# USB_OTG.net
KiCad netlist of a schematic drawn in Altium Designer
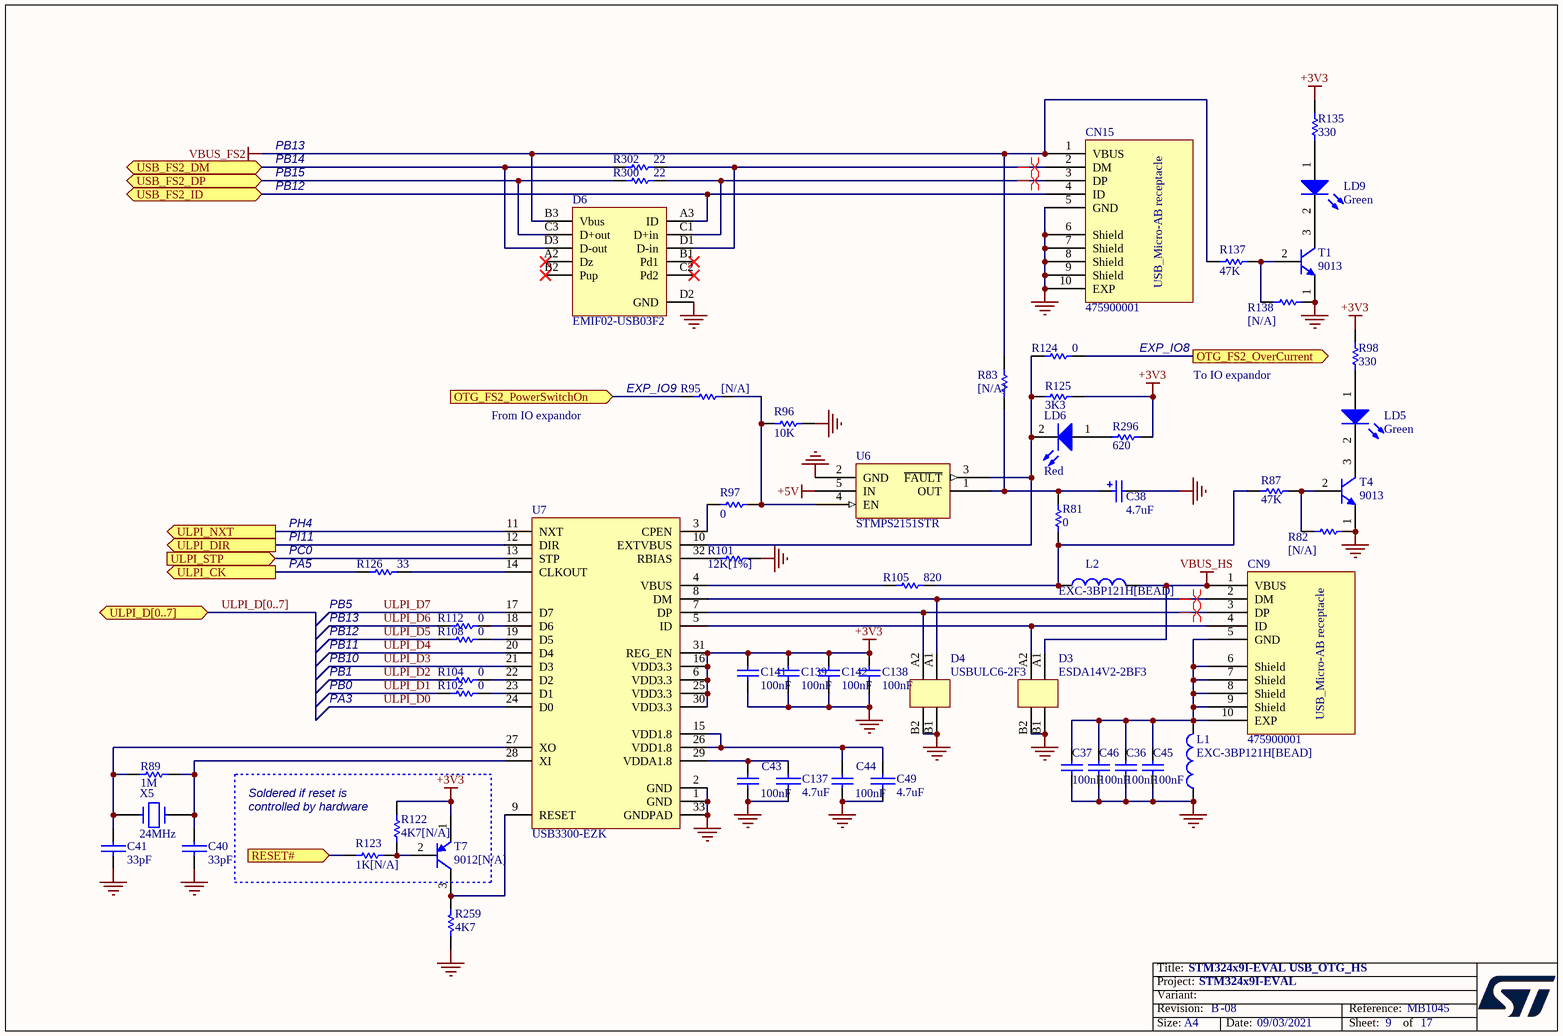
[diagram p0: USB_OTG.SchDoc]

(export (version "E")
  (design (tool "Eeschema 10.0.6"))
  (components
    (comp (ref "C36")
      (value "100nF")
      (footprint "0603C")
      (description "Capacitor")
      (fields (field (name "PUBLISHER") "Altium Limited"))
      (libsource (lib "Miscellaneous Devices") (part "Cap"))
    )
    (comp (ref "C37")
      (value "100nF")
      (footprint "0603C")
      (description "Capacitor")
      (fields (field (name "PUBLISHER") "Altium Limited"))
      (libsource (lib "Miscellaneous Devices") (part "Cap"))
    )
    (comp (ref "C38")
      (value "4.7uF")
      (footprint "TAN-A")
      (description "Polarized Capacitor (Radial)")
      (fields (field (name "PUBLISHER") "Altium Limited"))
      (libsource (lib "Miscellaneous Devices") (part "Cap Pol1"))
    )
    (comp (ref "C40")
      (value "33pF")
      (footprint "0603C")
      (description "Capacitor")
      (libsource (lib "*") (part "CAP"))
    )
    (comp (ref "C41")
      (value "33pF")
      (footprint "0603C")
      (description "Capacitor")
      (libsource (lib "*") (part "CAP"))
    )
    (comp (ref "C43")
      (value "100nF")
      (footprint "0603C")
      (description "Capacitor")
      (fields (field (name "PUBLISHER") "Altium Limited"))
      (libsource (lib "Miscellaneous Devices") (part "Cap"))
    )
    (comp (ref "C44")
      (value "100nF")
      (footprint "0603C")
      (description "Capacitor")
      (fields (field (name "PUBLISHER") "Altium Limited"))
      (libsource (lib "Miscellaneous Devices") (part "Cap"))
    )
    (comp (ref "C45")
      (value "100nF")
      (footprint "0603C")
      (description "Capacitor")
      (fields (field (name "PUBLISHER") "Altium Limited"))
      (libsource (lib "Miscellaneous Devices") (part "Cap"))
    )
    (comp (ref "C46")
      (value "100nF")
      (footprint "0603C")
      (description "Capacitor")
      (fields (field (name "PUBLISHER") "Altium Limited"))
      (libsource (lib "Miscellaneous Devices") (part "Cap"))
    )
    (comp (ref "C49")
      (value "4.7uF")
      (footprint "TAN-A")
      (description "Capacitor")
      (libsource (lib "") (part "CAP_1"))
    )
    (comp (ref "C137")
      (value "4.7uF")
      (footprint "TAN-A")
      (description "Capacitor")
      (libsource (lib "") (part "CAP_1"))
    )
    (comp (ref "C138")
      (value "100nF")
      (footprint "0603C")
      (description "Capacitor")
      (fields (field (name "PUBLISHER") "Altium Limited"))
      (libsource (lib "Miscellaneous Devices") (part "Cap"))
    )
    (comp (ref "C139")
      (value "100nF")
      (footprint "0603C")
      (description "Capacitor")
      (fields (field (name "PUBLISHER") "Altium Limited"))
      (libsource (lib "Miscellaneous Devices") (part "Cap"))
    )
    (comp (ref "C141")
      (value "100nF")
      (footprint "0603C")
      (description "Capacitor")
      (fields (field (name "PUBLISHER") "Altium Limited"))
      (libsource (lib "Miscellaneous Devices") (part "Cap"))
    )
    (comp (ref "C142")
      (value "100nF")
      (footprint "0603C")
      (description "Capacitor")
      (fields (field (name "PUBLISHER") "Altium Limited"))
      (libsource (lib "Miscellaneous Devices") (part "Cap"))
    )
    (comp (ref "CN9")
      (value "475900001")
      (footprint "MOLEX_47590001")
      (libsource (lib "mb1045") (part "475900001"))
    )
    (comp (ref "CN15")
      (value "475900001")
      (footprint "MOLEX_47590001")
      (libsource (lib "mb1045") (part "475900001"))
    )
    (comp (ref "D3")
      (value "ESDA14V2-2BF3")
      (footprint "BGA4_0R4_0R8X0R8")
      (libsource (lib "MB786") (part "ESDA14V2-2BF3"))
    )
    (comp (ref "D4")
      (value "USBULC6-2F3")
      (footprint "BGA4_0R4_1X1")
      (libsource (lib "MB786") (part "USBULC6-2F3"))
    )
    (comp (ref "D6")
      (value "EMIF02-USB03F2")
      (footprint "BGA11_0R5_1R57X2R07")
      (libsource (lib "mb1045") (part "EMIF02-USB03F2"))
    )
    (comp (ref "L1")
      (value "EXC-3BP121H[BEAD]")
      (footprint "0603L")
      (description "Inductor")
      (fields (field (name "PUBLISHER") "Altium Limited"))
      (libsource (lib "Miscellaneous Devices") (part "Inductor"))
    )
    (comp (ref "L2")
      (value "EXC-3BP121H[BEAD]")
      (footprint "0603L")
      (description "Inductor")
      (fields (field (name "PUBLISHER") "Altium Limited"))
      (libsource (lib "Miscellaneous Devices") (part "Inductor"))
    )
    (comp (ref "LD5")
      (value "Green")
      (footprint "0603D")
      (description "Typical RED, GREEN, YELLOW, AMBER GaAs LED")
      (fields (field (name "PUBLISHER") "Altium Limited"))
      (libsource (lib "Miscellaneous Devices") (part "LED2"))
    )
    (comp (ref "LD6")
      (value "Red")
      (footprint "0603D")
      (description "Typical RED, GREEN, YELLOW, AMBER GaAs LED")
      (fields (field (name "PUBLISHER") "Altium Limited"))
      (libsource (lib "Miscellaneous Devices") (part "LED2"))
    )
    (comp (ref "LD9")
      (value "Green")
      (footprint "0603D")
      (description "Typical RED, GREEN, YELLOW, AMBER GaAs LED")
      (fields (field (name "PUBLISHER") "Altium Limited"))
      (libsource (lib "Miscellaneous Devices") (part "LED2"))
    )
    (comp (ref "R81")
      (value "0")
      (footprint "0603R")
      (description "Resistor")
      (fields (field (name "PUBLISHER") "Altium Limited"))
      (libsource (lib "Miscellaneous Devices") (part "Res1"))
    )
    (comp (ref "R82")
      (value "[N/A]")
      (footprint "0603R")
      (description "Resistor")
      (fields (field (name "PUBLISHER") "Altium Limited"))
      (libsource (lib "Miscellaneous Devices") (part "res1"))
    )
    (comp (ref "R83")
      (value "[N/A]")
      (footprint "0603R")
      (description "Resistor")
      (fields (field (name "PUBLISHER") "Altium Limited"))
      (libsource (lib "Miscellaneous Devices") (part "Res1"))
    )
    (comp (ref "R87")
      (value "47K")
      (footprint "0603R")
      (description "Resistor")
      (fields (field (name "PUBLISHER") "Altium Limited"))
      (libsource (lib "Miscellaneous Devices") (part "res1"))
    )
    (comp (ref "R89")
      (value "1M")
      (footprint "0603R")
      (description "Resistor")
      (fields (field (name "PUBLISHER") "Altium Limited"))
      (libsource (lib "Miscellaneous Devices") (part "Res1"))
    )
    (comp (ref "R95")
      (value "[N/A]")
      (footprint "0603R")
      (description "Resistor")
      (fields (field (name "PUBLISHER") "Altium Limited"))
      (libsource (lib "Miscellaneous Devices") (part "Res1"))
    )
    (comp (ref "R96")
      (value "10K")
      (footprint "0603R")
      (description "Resistor")
      (fields (field (name "PUBLISHER") "Altium Limited"))
      (libsource (lib "Miscellaneous Devices") (part "res1"))
    )
    (comp (ref "R97")
      (value "0")
      (footprint "0603R")
      (description "Resistor")
      (fields (field (name "PUBLISHER") "Altium Limited"))
      (libsource (lib "Miscellaneous Devices") (part "Res1"))
    )
    (comp (ref "R98")
      (value "330")
      (footprint "0603R")
      (description "Resistor")
      (fields (field (name "PUBLISHER") "Altium Limited"))
      (libsource (lib "Miscellaneous Devices") (part "res1"))
    )
    (comp (ref "R101")
      (value "12K[1%]")
      (footprint "0603R")
      (description "Resistor")
      (fields (field (name "PUBLISHER") "Altium Limited"))
      (libsource (lib "Miscellaneous Devices") (part "Res1"))
    )
    (comp (ref "R102")
      (value "0")
      (footprint "0603R")
      (description "Resistor")
      (fields (field (name "PUBLISHER") "Altium Limited"))
      (libsource (lib "Miscellaneous Devices") (part "Res1"))
    )
    (comp (ref "R104")
      (value "0")
      (footprint "0603R")
      (description "Resistor")
      (fields (field (name "PUBLISHER") "Altium Limited"))
      (libsource (lib "Miscellaneous Devices") (part "Res1"))
    )
    (comp (ref "R105")
      (value "820")
      (footprint "0603R")
      (description "Resistor")
      (fields (field (name "PUBLISHER") "Altium Limited"))
      (libsource (lib "Miscellaneous Devices") (part "res1"))
    )
    (comp (ref "R108")
      (value "0")
      (footprint "0603R")
      (description "Resistor")
      (fields (field (name "PUBLISHER") "Altium Limited"))
      (libsource (lib "Miscellaneous Devices") (part "Res1"))
    )
    (comp (ref "R112")
      (value "0")
      (footprint "0603R")
      (description "Resistor")
      (fields (field (name "PUBLISHER") "Altium Limited"))
      (libsource (lib "Miscellaneous Devices") (part "Res1"))
    )
    (comp (ref "R122")
      (value "4K7[N/A]")
      (footprint "0603R")
      (description "Resistor")
      (fields (field (name "PUBLISHER") "Altium Limited"))
      (libsource (lib "*") (part "Res1"))
    )
    (comp (ref "R123")
      (value "1K[N/A]")
      (footprint "0603R")
      (description "Resistor")
      (fields (field (name "PUBLISHER") "Altium Limited"))
      (libsource (lib "Miscellaneous Devices") (part "Res1"))
    )
    (comp (ref "R124")
      (value "0")
      (footprint "0603R")
      (description "Resistor")
      (fields (field (name "PUBLISHER") "Altium Limited"))
      (libsource (lib "Miscellaneous Devices") (part "Res1"))
    )
    (comp (ref "R125")
      (value "3K3")
      (footprint "0603R")
      (description "Resistor")
      (fields (field (name "PUBLISHER") "Altium Limited"))
      (libsource (lib "Miscellaneous Devices") (part "res1"))
    )
    (comp (ref "R126")
      (value "33")
      (footprint "0603R")
      (description "Resistor")
      (fields (field (name "PUBLISHER") "Altium Limited"))
      (libsource (lib "Miscellaneous Devices") (part "Res1"))
    )
    (comp (ref "R135")
      (value "330")
      (footprint "0603R")
      (description "Resistor")
      (fields (field (name "PUBLISHER") "Altium Limited"))
      (libsource (lib "Miscellaneous Devices") (part "res1"))
    )
    (comp (ref "R137")
      (value "47K")
      (footprint "0603R")
      (description "Resistor")
      (fields (field (name "PUBLISHER") "Altium Limited"))
      (libsource (lib "Miscellaneous Devices") (part "res1"))
    )
    (comp (ref "R138")
      (value "[N/A]")
      (footprint "0603R")
      (description "Resistor")
      (fields (field (name "PUBLISHER") "Altium Limited"))
      (libsource (lib "Miscellaneous Devices") (part "res1"))
    )
    (comp (ref "R259")
      (value "4K7")
      (footprint "0603R")
      (description "Resistor")
      (fields (field (name "PUBLISHER") "Altium Limited"))
      (libsource (lib "*") (part "Res1"))
    )
    (comp (ref "R296")
      (value "620")
      (footprint "0603R")
      (description "Resistor")
      (fields (field (name "PUBLISHER") "Altium Limited"))
      (libsource (lib "Miscellaneous Devices") (part "Res1"))
    )
    (comp (ref "R300")
      (value "22")
      (footprint "0603R")
      (description "Resistor")
      (fields (field (name "PUBLISHER") "Altium Limited"))
      (libsource (lib "Miscellaneous Devices") (part "Res1"))
    )
    (comp (ref "R302")
      (value "22")
      (footprint "0603R")
      (description "Resistor")
      (fields (field (name "PUBLISHER") "Altium Limited"))
      (libsource (lib "Miscellaneous Devices") (part "Res1"))
    )
    (comp (ref "T1")
      (value "9013")
      (footprint "SOT23-213")
      (description "NPN Bipolar Transistor")
      (fields (field (name "PUBLISHER") "Altium Limited"))
      (libsource (lib "mb1045") (part "NPN"))
    )
    (comp (ref "T4")
      (value "9013")
      (footprint "SOT23-213")
      (description "NPN Bipolar Transistor")
      (fields (field (name "PUBLISHER") "Altium Limited"))
      (libsource (lib "mb1045") (part "NPN"))
    )
    (comp (ref "T7")
      (value "9012[N/A]")
      (footprint "SOT23-213")
      (description "PNP Bipolar Transistor")
      (fields (field (name "PUBLISHER") "Altium Limited"))
      (libsource (lib "Miscellaneous Devices") (part "PNP"))
    )
    (comp (ref "U6")
      (value "STMPS2151STR")
      (footprint "SOT23-5")
      (libsource (lib "mb1045") (part "STMPS2141STR"))
    )
    (comp (ref "U7")
      (value "USB3300-EZK")
      (footprint "QFN32_0R5_5X5")
      (libsource (lib "MB1000_1") (part "USB3300-EZK"))
    )
    (comp (ref "X5")
      (value "24MHz")
      (footprint "XTAL1")
      (description "Crystal")
      (libsource (lib "*") (part "CRYSTAL"))
    )
  )
  (nets
    (net (code "1") (name "+3V3") (class "Default")
      (node (ref "C138") (pin "1") (pinfunction "1_1") (pintype "passive"))
      (node (ref "C139") (pin "1") (pinfunction "1_1") (pintype "passive"))
      (node (ref "C141") (pin "1") (pinfunction "1_1") (pintype "passive"))
      (node (ref "C142") (pin "1") (pinfunction "1_1") (pintype "passive"))
      (node (ref "R122") (pin "1") (pinfunction "1_1") (pintype "passive"))
      (node (ref "R125") (pin "1") (pinfunction "1_1") (pintype "passive"))
      (node (ref "R135") (pin "2") (pinfunction "2_2") (pintype "passive"))
      (node (ref "R296") (pin "2") (pinfunction "2_2") (pintype "passive"))
      (node (ref "R98") (pin "2") (pinfunction "2_2") (pintype "passive"))
      (node (ref "T7") (pin "1") (pinfunction "E_1") (pintype "passive"))
      (node (ref "U7") (pin "16") (pinfunction "VDD3.3_16") (pintype "passive"))
      (node (ref "U7") (pin "25") (pinfunction "VDD3.3_25") (pintype "passive"))
      (node (ref "U7") (pin "30") (pinfunction "VDD3.3_30") (pintype "passive"))
      (node (ref "U7") (pin "31") (pinfunction "REG_EN_31") (pintype "passive"))
      (node (ref "U7") (pin "6") (pinfunction "VDD3.3_6") (pintype "passive"))
    )
    (net (code "2") (name "+5V") (class "Default")
      (node (ref "U6") (pin "5") (pinfunction "IN_5") (pintype "passive"))
    )
    (net (code "3") (name "/OTG_FS2_OverCurrent") (class "Default")
      (node (ref "R124") (pin "1") (pinfunction "1_1") (pintype "passive"))
    )
    (net (code "4") (name "/OTG_FS2_PowerSwitchOn") (class "Default")
      (node (ref "R95") (pin "2") (pinfunction "2_2") (pintype "passive"))
    )
    (net (code "5") (name "/RESET#") (class "Default")
      (node (ref "R123") (pin "2") (pinfunction "2_2") (pintype "passive"))
    )
    (net (code "6") (name "/ULPI_CK") (class "Default")
      (node (ref "R126") (pin "2") (pinfunction "2_2") (pintype "passive"))
    )
    (net (code "7") (name "/ULPI_D0") (class "Default")
      (node (ref "U7") (pin "24") (pinfunction "D0_24") (pintype "passive"))
    )
    (net (code "8") (name "/ULPI_D1") (class "Default")
      (node (ref "R102") (pin "2") (pinfunction "2_2") (pintype "passive"))
    )
    (net (code "9") (name "/ULPI_D2") (class "Default")
      (node (ref "R104") (pin "2") (pinfunction "2_2") (pintype "passive"))
    )
    (net (code "10") (name "/ULPI_D3") (class "Default")
      (node (ref "U7") (pin "21") (pinfunction "D3_21") (pintype "passive"))
    )
    (net (code "11") (name "/ULPI_D4") (class "Default")
      (node (ref "U7") (pin "20") (pinfunction "D4_20") (pintype "passive"))
    )
    (net (code "12") (name "/ULPI_D5") (class "Default")
      (node (ref "R108") (pin "2") (pinfunction "2_2") (pintype "passive"))
    )
    (net (code "13") (name "/ULPI_D6") (class "Default")
      (node (ref "R112") (pin "2") (pinfunction "2_2") (pintype "passive"))
    )
    (net (code "14") (name "/ULPI_D7") (class "Default")
      (node (ref "U7") (pin "17") (pinfunction "D7_17") (pintype "passive"))
    )
    (net (code "15") (name "/ULPI_DIR") (class "Default")
      (node (ref "U7") (pin "12") (pinfunction "DIR_12") (pintype "passive"))
    )
    (net (code "17") (name "/ULPI_NXT") (class "Default")
      (node (ref "U7") (pin "11") (pinfunction "NXT_11") (pintype "passive"))
    )
    (net (code "18") (name "/ULPI_STP") (class "Default")
      (node (ref "U7") (pin "13") (pinfunction "STP_13") (pintype "passive"))
    )
    (net (code "19") (name "/USB_FS2_DM") (class "Default")
      (node (ref "D6") (pin "D3") (pinfunction "D-out_D3") (pintype "passive"))
      (node (ref "R302") (pin "2") (pinfunction "2_2") (pintype "passive"))
    )
    (net (code "20") (name "/USB_FS2_DP") (class "Default")
      (node (ref "D6") (pin "C3") (pinfunction "D+out_C3") (pintype "passive"))
      (node (ref "R300") (pin "2") (pinfunction "2_2") (pintype "passive"))
    )
    (net (code "21") (name "/USB_FS2_ID") (class "Default")
      (node (ref "CN15") (pin "4") (pinfunction "ID_4") (pintype "passive"))
      (node (ref "D6") (pin "A3") (pinfunction "ID_A3") (pintype "passive"))
    )
    (net (code "22") (name "GND") (class "Default")
      (node (ref "C137") (pin "2") (pinfunction "2_2") (pintype "passive"))
      (node (ref "C138") (pin "2") (pinfunction "2_2") (pintype "passive"))
      (node (ref "C139") (pin "2") (pinfunction "2_2") (pintype "passive"))
      (node (ref "C141") (pin "2") (pinfunction "2_2") (pintype "passive"))
      (node (ref "C142") (pin "2") (pinfunction "2_2") (pintype "passive"))
      (node (ref "C36") (pin "2") (pinfunction "2_2") (pintype "passive"))
      (node (ref "C37") (pin "2") (pinfunction "2_2") (pintype "passive"))
      (node (ref "C38") (pin "2") (pinfunction "2_2") (pintype "passive"))
      (node (ref "C40") (pin "2") (pinfunction "2_2") (pintype "passive"))
      (node (ref "C41") (pin "2") (pinfunction "2_2") (pintype "passive"))
      (node (ref "C43") (pin "2") (pinfunction "2_2") (pintype "passive"))
      (node (ref "C44") (pin "2") (pinfunction "2_2") (pintype "passive"))
      (node (ref "C45") (pin "2") (pinfunction "2_2") (pintype "passive"))
      (node (ref "C46") (pin "2") (pinfunction "2_2") (pintype "passive"))
      (node (ref "C49") (pin "2") (pinfunction "2_2") (pintype "passive"))
      (node (ref "CN15") (pin "10") (pinfunction "EXP_10") (pintype "passive"))
      (node (ref "CN15") (pin "5") (pinfunction "GND_5") (pintype "passive"))
      (node (ref "CN15") (pin "6") (pinfunction "Shield_6") (pintype "passive"))
      (node (ref "CN15") (pin "7") (pinfunction "Shield_7") (pintype "passive"))
      (node (ref "CN15") (pin "8") (pinfunction "Shield_8") (pintype "passive"))
      (node (ref "CN15") (pin "9") (pinfunction "Shield_9") (pintype "passive"))
      (node (ref "D3") (pin "B1") (pintype "passive"))
      (node (ref "D3") (pin "B2") (pintype "passive"))
      (node (ref "D4") (pin "B1") (pintype "passive"))
      (node (ref "D4") (pin "B2") (pintype "passive"))
      (node (ref "D6") (pin "D2") (pinfunction "GND_D2") (pintype "passive"))
      (node (ref "L1") (pin "1") (pinfunction "1_1") (pintype "passive"))
      (node (ref "R101") (pin "1") (pinfunction "1_1") (pintype "passive"))
      (node (ref "R138") (pin "1") (pinfunction "1_1") (pintype "passive"))
      (node (ref "R259") (pin "1") (pinfunction "1_1") (pintype "passive"))
      (node (ref "R82") (pin "1") (pinfunction "1_1") (pintype "passive"))
      (node (ref "R96") (pin "1") (pinfunction "1_1") (pintype "passive"))
      (node (ref "T1") (pin "1") (pinfunction "E_1") (pintype "passive"))
      (node (ref "T4") (pin "1") (pinfunction "E_1") (pintype "passive"))
      (node (ref "U6") (pin "2") (pinfunction "GND_2") (pintype "passive"))
      (node (ref "U7") (pin "1") (pinfunction "GND_1") (pintype "passive"))
      (node (ref "U7") (pin "2") (pinfunction "GND_2") (pintype "passive"))
      (node (ref "U7") (pin "33") (pinfunction "GNDPAD_33") (pintype "passive"))
    )
    (net (code "23") (name "Net-(C44-Pad1)") (class "Default")
      (node (ref "C44") (pin "1") (pinfunction "1_1") (pintype "passive"))
      (node (ref "C49") (pin "1") (pinfunction "1_1") (pintype "passive"))
      (node (ref "U7") (pin "15") (pinfunction "VDD1.8_15") (pintype "passive"))
      (node (ref "U7") (pin "26") (pinfunction "VDD1.8_26") (pintype "passive"))
    )
    (net (code "24") (name "Net-(CN9-DM)") (class "Default")
      (node (ref "CN9") (pin "2") (pinfunction "DM_2") (pintype "passive"))
      (node (ref "D4") (pin "A1") (pintype "passive"))
      (node (ref "U7") (pin "8") (pinfunction "DM_8") (pintype "passive"))
    )
    (net (code "25") (name "Net-(CN9-DP)") (class "Default")
      (node (ref "CN9") (pin "3") (pinfunction "DP_3") (pintype "passive"))
      (node (ref "D4") (pin "A2") (pintype "passive"))
      (node (ref "U7") (pin "7") (pinfunction "DP_7") (pintype "passive"))
    )
    (net (code "26") (name "Net-(CN9-EXP)") (class "Default")
      (node (ref "C36") (pin "1") (pinfunction "1_1") (pintype "passive"))
      (node (ref "C37") (pin "1") (pinfunction "1_1") (pintype "passive"))
      (node (ref "C45") (pin "1") (pinfunction "1_1") (pintype "passive"))
      (node (ref "C46") (pin "1") (pinfunction "1_1") (pintype "passive"))
      (node (ref "CN9") (pin "10") (pinfunction "EXP_10") (pintype "passive"))
      (node (ref "CN9") (pin "5") (pinfunction "GND_5") (pintype "passive"))
      (node (ref "CN9") (pin "6") (pinfunction "Shield_6") (pintype "passive"))
      (node (ref "CN9") (pin "7") (pinfunction "Shield_7") (pintype "passive"))
      (node (ref "CN9") (pin "8") (pinfunction "Shield_8") (pintype "passive"))
      (node (ref "CN9") (pin "9") (pinfunction "Shield_9") (pintype "passive"))
      (node (ref "L1") (pin "2") (pinfunction "2_2") (pintype "passive"))
    )
    (net (code "27") (name "Net-(CN9-ID)") (class "Default")
      (node (ref "CN9") (pin "4") (pinfunction "ID_4") (pintype "passive"))
      (node (ref "D3") (pin "A2") (pintype "passive"))
      (node (ref "U7") (pin "5") (pinfunction "ID_5") (pintype "passive"))
    )
    (net (code "28") (name "Net-(CN15-DM)") (class "Default")
      (node (ref "CN15") (pin "2") (pinfunction "DM_2") (pintype "passive"))
      (node (ref "D6") (pin "D1") (pinfunction "D-in_D1") (pintype "passive"))
      (node (ref "R302") (pin "1") (pinfunction "1_1") (pintype "passive"))
    )
    (net (code "29") (name "Net-(CN15-DP)") (class "Default")
      (node (ref "CN15") (pin "3") (pinfunction "DP_3") (pintype "passive"))
      (node (ref "D6") (pin "C1") (pinfunction "D+in_C1") (pintype "passive"))
      (node (ref "R300") (pin "1") (pinfunction "1_1") (pintype "passive"))
    )
    (net (code "30") (name "Net-(L2-Pad1)") (class "Default")
      (node (ref "L2") (pin "1") (pinfunction "1_1") (pintype "passive"))
      (node (ref "R105") (pin "2") (pinfunction "2_2") (pintype "passive"))
      (node (ref "R81") (pin "2") (pinfunction "2_2") (pintype "passive"))
      (node (ref "R87") (pin "2") (pinfunction "2_2") (pintype "passive"))
    )
    (net (code "31") (name "Net-(LD5-A)") (class "Default")
      (node (ref "LD5") (pin "1") (pinfunction "A_1") (pintype "passive"))
      (node (ref "R98") (pin "1") (pinfunction "1_1") (pintype "passive"))
    )
    (net (code "32") (name "Net-(LD5-K)") (class "Default")
      (node (ref "LD5") (pin "2") (pinfunction "K_2") (pintype "passive"))
      (node (ref "T4") (pin "3") (pinfunction "C_3") (pintype "passive"))
    )
    (net (code "33") (name "Net-(LD6-A)") (class "Default")
      (node (ref "LD6") (pin "1") (pinfunction "A_1") (pintype "passive"))
      (node (ref "R296") (pin "1") (pinfunction "1_1") (pintype "passive"))
    )
    (net (code "34") (name "Net-(LD6-K)") (class "Default")
      (node (ref "LD6") (pin "2") (pinfunction "K_2") (pintype "passive"))
      (node (ref "R124") (pin "2") (pinfunction "2_2") (pintype "passive"))
      (node (ref "R125") (pin "2") (pinfunction "2_2") (pintype "passive"))
      (node (ref "U6") (pin "3") (pinfunction "~{FAULT}_3") (pintype "output"))
      (node (ref "U7") (pin "10") (pinfunction "EXTVBUS_10") (pintype "passive"))
    )
    (net (code "35") (name "Net-(LD9-A)") (class "Default")
      (node (ref "LD9") (pin "1") (pinfunction "A_1") (pintype "passive"))
      (node (ref "R135") (pin "1") (pinfunction "1_1") (pintype "passive"))
    )
    (net (code "36") (name "Net-(LD9-K)") (class "Default")
      (node (ref "LD9") (pin "2") (pinfunction "K_2") (pintype "passive"))
      (node (ref "T1") (pin "3") (pinfunction "C_3") (pintype "passive"))
    )
    (net (code "37") (name "Net-(T1-B)") (class "Default")
      (node (ref "R137") (pin "2") (pinfunction "2_2") (pintype "passive"))
      (node (ref "R138") (pin "2") (pinfunction "2_2") (pintype "passive"))
      (node (ref "T1") (pin "2") (pinfunction "B_2") (pintype "passive"))
    )
    (net (code "38") (name "Net-(T4-B)") (class "Default")
      (node (ref "R82") (pin "2") (pinfunction "2_2") (pintype "passive"))
      (node (ref "R87") (pin "1") (pinfunction "1_1") (pintype "passive"))
      (node (ref "T4") (pin "2") (pinfunction "B_2") (pintype "passive"))
    )
    (net (code "39") (name "Net-(T7-B)") (class "Default")
      (node (ref "R122") (pin "2") (pinfunction "2_2") (pintype "passive"))
      (node (ref "R123") (pin "1") (pinfunction "1_1") (pintype "passive"))
      (node (ref "T7") (pin "2") (pinfunction "B_2") (pintype "passive"))
    )
    (net (code "40") (name "Net-(T7-C)") (class "Default")
      (node (ref "R259") (pin "2") (pinfunction "2_2") (pintype "passive"))
      (node (ref "T7") (pin "3") (pinfunction "C_3") (pintype "passive"))
      (node (ref "U7") (pin "9") (pinfunction "RESET_9") (pintype "passive"))
    )
    (net (code "41") (name "Net-(U6-EN)") (class "Default")
      (node (ref "R95") (pin "1") (pinfunction "1_1") (pintype "passive"))
      (node (ref "R96") (pin "2") (pinfunction "2_2") (pintype "passive"))
      (node (ref "R97") (pin "2") (pinfunction "2_2") (pintype "passive"))
      (node (ref "U6") (pin "4") (pinfunction "EN_4") (pintype "input"))
    )
    (net (code "42") (name "Net-(U6-OUT)") (class "Default")
      (node (ref "C38") (pin "1") (pinfunction "1_1") (pintype "passive"))
      (node (ref "R81") (pin "1") (pinfunction "1_1") (pintype "passive"))
      (node (ref "R83") (pin "2") (pinfunction "2_2") (pintype "passive"))
      (node (ref "U6") (pin "1") (pinfunction "OUT_1") (pintype "passive"))
    )
    (net (code "43") (name "Net-(U7-CLKOUT)") (class "Default")
      (node (ref "R126") (pin "1") (pinfunction "1_1") (pintype "passive"))
      (node (ref "U7") (pin "14") (pinfunction "CLKOUT_14") (pintype "passive"))
    )
    (net (code "44") (name "Net-(U7-CPEN)") (class "Default")
      (node (ref "R97") (pin "1") (pinfunction "1_1") (pintype "passive"))
      (node (ref "U7") (pin "3") (pinfunction "CPEN_3") (pintype "passive"))
    )
    (net (code "45") (name "Net-(U7-D1)") (class "Default")
      (node (ref "R102") (pin "1") (pinfunction "1_1") (pintype "passive"))
      (node (ref "U7") (pin "23") (pinfunction "D1_23") (pintype "passive"))
    )
    (net (code "46") (name "Net-(U7-D2)") (class "Default")
      (node (ref "R104") (pin "1") (pinfunction "1_1") (pintype "passive"))
      (node (ref "U7") (pin "22") (pinfunction "D2_22") (pintype "passive"))
    )
    (net (code "47") (name "Net-(U7-D5)") (class "Default")
      (node (ref "R108") (pin "1") (pinfunction "1_1") (pintype "passive"))
      (node (ref "U7") (pin "19") (pinfunction "D5_19") (pintype "passive"))
    )
    (net (code "48") (name "Net-(U7-D6)") (class "Default")
      (node (ref "R112") (pin "1") (pinfunction "1_1") (pintype "passive"))
      (node (ref "U7") (pin "18") (pinfunction "D6_18") (pintype "passive"))
    )
    (net (code "49") (name "Net-(U7-RBIAS)") (class "Default")
      (node (ref "R101") (pin "2") (pinfunction "2_2") (pintype "passive"))
      (node (ref "U7") (pin "32") (pinfunction "RBIAS_32") (pintype "passive"))
    )
    (net (code "50") (name "Net-(U7-VBUS)") (class "Default")
      (node (ref "R105") (pin "1") (pinfunction "1_1") (pintype "passive"))
      (node (ref "U7") (pin "4") (pinfunction "VBUS_4") (pintype "passive"))
    )
    (net (code "51") (name "Net-(U7-VDDA1.8)") (class "Default")
      (node (ref "C137") (pin "1") (pinfunction "1_1") (pintype "passive"))
      (node (ref "C43") (pin "1") (pinfunction "1_1") (pintype "passive"))
      (node (ref "U7") (pin "29") (pinfunction "VDDA1.8_29") (pintype "passive"))
    )
    (net (code "52") (name "Net-(U7-XI)") (class "Default")
      (node (ref "C40") (pin "1") (pinfunction "1_1") (pintype "passive"))
      (node (ref "R89") (pin "2") (pinfunction "2_2") (pintype "passive"))
      (node (ref "U7") (pin "28") (pinfunction "XI_28") (pintype "passive"))
      (node (ref "X5") (pin "1") (pinfunction "1_1") (pintype "passive"))
    )
    (net (code "53") (name "Net-(U7-XO)") (class "Default")
      (node (ref "C41") (pin "1") (pinfunction "1_1") (pintype "passive"))
      (node (ref "R89") (pin "1") (pinfunction "1_1") (pintype "passive"))
      (node (ref "U7") (pin "27") (pinfunction "XO_27") (pintype "passive"))
      (node (ref "X5") (pin "2") (pinfunction "2_2") (pintype "passive"))
    )
    (net (code "54") (name "VBUS_FS2") (class "Default")
      (node (ref "CN15") (pin "1") (pinfunction "VBUS_1") (pintype "passive"))
      (node (ref "D6") (pin "B3") (pinfunction "Vbus_B3") (pintype "passive"))
      (node (ref "R137") (pin "1") (pinfunction "1_1") (pintype "passive"))
      (node (ref "R83") (pin "1") (pinfunction "1_1") (pintype "passive"))
    )
    (net (code "55") (name "VBUS_HS") (class "Default")
      (node (ref "CN9") (pin "1") (pinfunction "VBUS_1") (pintype "passive"))
      (node (ref "D3") (pin "A1") (pintype "passive"))
      (node (ref "L2") (pin "2") (pinfunction "2_2") (pintype "passive"))
    )
    (net (code "56") (name "unconnected-(D6-Dz-PadA2)") (class "Default")
      (node (ref "D6") (pin "A2") (pinfunction "Dz_A2") (pintype "passive+no_connect"))
    )
    (net (code "57") (name "unconnected-(D6-Pd1-PadB1)") (class "Default")
      (node (ref "D6") (pin "B1") (pinfunction "Pd1_B1") (pintype "passive+no_connect"))
    )
    (net (code "58") (name "unconnected-(D6-Pd2-PadC2)") (class "Default")
      (node (ref "D6") (pin "C2") (pinfunction "Pd2_C2") (pintype "passive+no_connect"))
    )
    (net (code "59") (name "unconnected-(D6-Pup-PadB2)") (class "Default")
      (node (ref "D6") (pin "B2") (pinfunction "Pup_B2") (pintype "passive+no_connect"))
    )
  )
)
